# Vertrangingsschema_schema.net
KiCad netlist of a schematic drawn in EAGLE
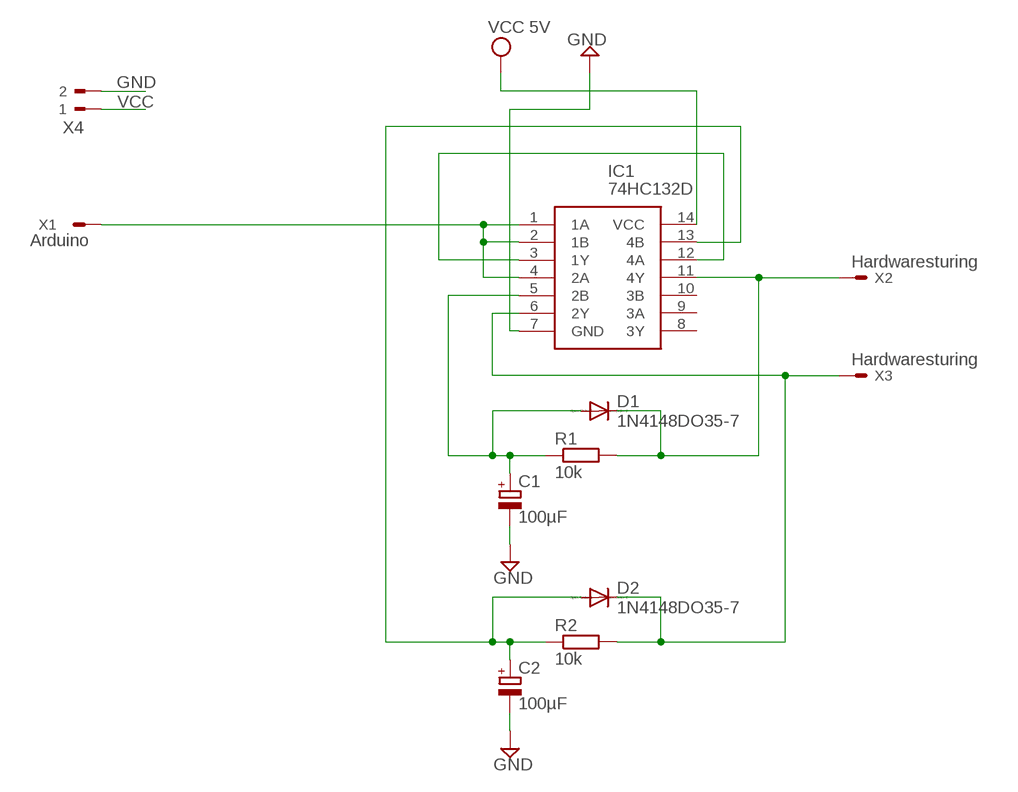
[diagram p0: schematic, sheet 1]

(export (version "E")
  (design (tool "Eeschema 10.0.6"))
  (components
    (comp (ref "C1")
      (value "100µF")
      (footprint "eagle-import:E3,5-8")
      (libsource (lib "eagle-import") (part "ELCO"))
    )
    (comp (ref "C2")
      (value "100µF")
      (footprint "eagle-import:E3,5-8")
      (libsource (lib "eagle-import") (part "ELCO"))
    )
    (comp (ref "D1")
      (value "1N4148DO35-7")
      (footprint "eagle-import:DO35-7")
      (libsource (lib "eagle-import") (part "1N4148DO35-7"))
    )
    (comp (ref "D2")
      (value "1N4148DO35-7")
      (footprint "eagle-import:DO35-7")
      (libsource (lib "eagle-import") (part "1N4148DO35-7"))
    )
    (comp (ref "IC1")
      (value "74HC132D")
      (footprint "eagle-import:SOIC127P600X175-14N")
      (fields (field (name "RS_PART_NUMBER") "4367408"))
      (libsource (lib "eagle-import") (part "74HC132D"))
    )
    (comp (ref "R1")
      (value "10k")
      (footprint "eagle-import:RDH_15")
      (libsource (lib "eagle-import") (part "RESISTOR"))
    )
    (comp (ref "R2")
      (value "10k")
      (footprint "eagle-import:RDH_15")
      (libsource (lib "eagle-import") (part "RESISTOR"))
    )
    (comp (ref "X1")
      (value "Arduino")
      (footprint "eagle-import:332-02")
      (libsource (lib "eagle-import") (part "332-02"))
    )
    (comp (ref "X2")
      (value "Hardwaresturing")
      (footprint "eagle-import:332-02")
      (libsource (lib "eagle-import") (part "332-02"))
    )
    (comp (ref "X3")
      (value "Hardwaresturing")
      (footprint "eagle-import:332-02")
      (libsource (lib "eagle-import") (part "332-02"))
    )
    (comp (ref "X4")
      (value "90-2")
      (footprint "eagle-import:90-2")
      (libsource (lib "eagle-import") (part "90-2"))
    )
  )
  (nets
    (net (code "1") (name "GND") (class "Default")
      (node (ref "C1") (pin "-") (pinfunction "-_-") (pintype "passive"))
      (node (ref "C2") (pin "-") (pinfunction "-_-") (pintype "passive"))
      (node (ref "IC1") (pin "7") (pinfunction "GND_7") (pintype "power_in"))
      (node (ref "X4") (pin "2") (pinfunction "2_2") (pintype "passive"))
    )
    (net (code "2") (name "Net-(IC1-1A)") (class "Default")
      (node (ref "IC1") (pin "1") (pinfunction "1A_1") (pintype "bidirectional"))
      (node (ref "IC1") (pin "2") (pinfunction "1B_2") (pintype "bidirectional"))
      (node (ref "IC1") (pin "4") (pinfunction "2A_4") (pintype "bidirectional"))
      (node (ref "X1") (pin "1") (pinfunction "S_1") (pintype "passive"))
    )
    (net (code "3") (name "Net-(IC1-1Y)") (class "Default")
      (node (ref "IC1") (pin "12") (pinfunction "4A_12") (pintype "bidirectional"))
      (node (ref "IC1") (pin "3") (pinfunction "1Y_3") (pintype "bidirectional"))
    )
    (net (code "4") (name "Net-(IC1-2B)") (class "Default")
      (node (ref "C1") (pin "+") (pinfunction "+_+") (pintype "passive"))
      (node (ref "D1") (pin "A") (pinfunction "A_A") (pintype "passive"))
      (node (ref "IC1") (pin "5") (pinfunction "2B_5") (pintype "bidirectional"))
      (node (ref "R1") (pin "1") (pinfunction "1_1") (pintype "passive"))
    )
    (net (code "5") (name "Net-(IC1-2Y)") (class "Default")
      (node (ref "D2") (pin "C") (pinfunction "C_C") (pintype "passive"))
      (node (ref "IC1") (pin "6") (pinfunction "2Y_6") (pintype "bidirectional"))
      (node (ref "R2") (pin "2") (pinfunction "2_2") (pintype "passive"))
      (node (ref "X3") (pin "1") (pinfunction "S_1") (pintype "passive"))
    )
    (net (code "6") (name "Net-(IC1-4B)") (class "Default")
      (node (ref "C2") (pin "+") (pinfunction "+_+") (pintype "passive"))
      (node (ref "D2") (pin "A") (pinfunction "A_A") (pintype "passive"))
      (node (ref "IC1") (pin "13") (pinfunction "4B_13") (pintype "bidirectional"))
      (node (ref "R2") (pin "1") (pinfunction "1_1") (pintype "passive"))
    )
    (net (code "7") (name "Net-(IC1-4Y)") (class "Default")
      (node (ref "D1") (pin "C") (pinfunction "C_C") (pintype "passive"))
      (node (ref "IC1") (pin "11") (pinfunction "4Y_11") (pintype "bidirectional"))
      (node (ref "R1") (pin "2") (pinfunction "2_2") (pintype "passive"))
      (node (ref "X2") (pin "1") (pinfunction "S_1") (pintype "passive"))
    )
    (net (code "8") (name "VCC 5V") (class "Default")
      (node (ref "IC1") (pin "14") (pinfunction "VCC_14") (pintype "power_in"))
      (node (ref "X4") (pin "1") (pinfunction "1_1") (pintype "passive"))
    )
    (net (code "9") (name "unconnected-(IC1-3A-Pad9)") (class "Default")
      (node (ref "IC1") (pin "9") (pinfunction "3A_9") (pintype "bidirectional"))
    )
    (net (code "10") (name "unconnected-(IC1-3B-Pad10)") (class "Default")
      (node (ref "IC1") (pin "10") (pinfunction "3B_10") (pintype "bidirectional"))
    )
    (net (code "11") (name "unconnected-(IC1-3Y-Pad8)") (class "Default")
      (node (ref "IC1") (pin "8") (pinfunction "3Y_8") (pintype "bidirectional"))
    )
  )
)
